# voltageSupplies.net
KiCad netlist of a schematic drawn in Altium Designer
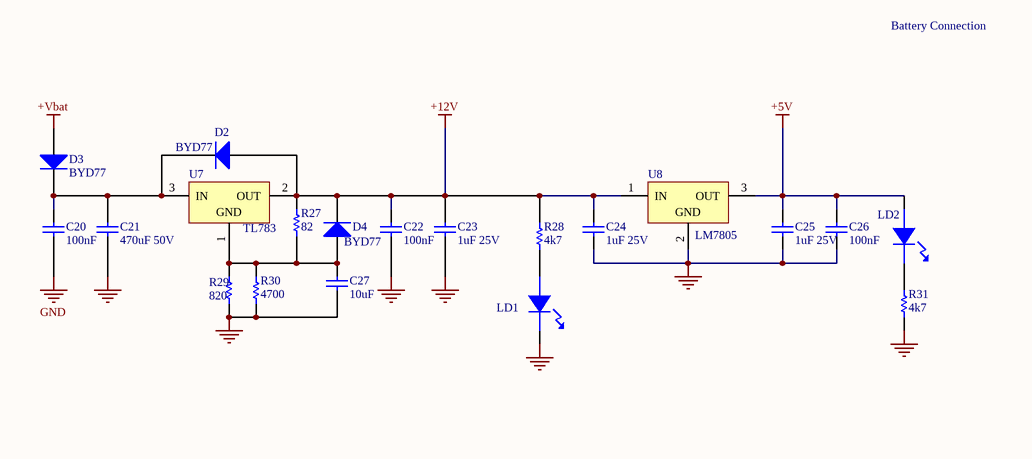
[diagram p0: voltageSupplies.SchDoc]

(export (version "E")
  (design (tool "Eeschema 10.0.6"))
  (components
    (comp (ref "C20")
      (value "100nF")
      (footprint "C1210_M")
      (description "Capacitor")
      (fields (field (name "Comment") "Cap") (field (name "PUBLISHER") "Altium Limited"))
      (libsource (lib "Miscellaneous Devices") (part "Cap"))
    )
    (comp (ref "C21")
      (value "470uF 50V")
      (footprint "CapEltr-Rad4.1-Dpp3.0")
      (description "Capacitor")
      (fields (field (name "Comment") "Cap") (field (name "PUBLISHER") "Altium Limited"))
      (libsource (lib "Miscellaneous Devices") (part "Cap"))
    )
    (comp (ref "C22")
      (value "100nF")
      (footprint "C1210_M")
      (description "Capacitor")
      (fields (field (name "Comment") "Cap") (field (name "PUBLISHER") "Altium Limited"))
      (libsource (lib "Miscellaneous Devices") (part "Cap"))
    )
    (comp (ref "C23")
      (value "1uF 25V")
      (footprint "CapEltr-Rad4.1-Dpp3.0")
      (description "Capacitor")
      (fields (field (name "Comment") "Cap") (field (name "PUBLISHER") "Altium Limited"))
      (libsource (lib "Miscellaneous Devices") (part "Cap"))
    )
    (comp (ref "C24")
      (value "1uF 25V")
      (footprint "CapEltr-Rad4.1-Dpp3.0")
      (description "Capacitor")
      (fields (field (name "Comment") "Cap") (field (name "PUBLISHER") "Altium Limited"))
      (libsource (lib "Miscellaneous Devices") (part "Cap"))
    )
    (comp (ref "C25")
      (value "1uF 25V")
      (footprint "CapEltr-Rad4.1-Dpp3.0")
      (description "Capacitor")
      (fields (field (name "Comment") "Cap") (field (name "PUBLISHER") "Altium Limited"))
      (libsource (lib "Miscellaneous Devices") (part "Cap"))
    )
    (comp (ref "C26")
      (value "100nF")
      (footprint "C1210_M")
      (description "Capacitor")
      (fields (field (name "Comment") "Cap") (field (name "PUBLISHER") "Altium Limited"))
      (libsource (lib "Miscellaneous Devices") (part "Cap"))
    )
    (comp (ref "C27")
      (value "10uF")
      (footprint "C1210_M")
      (description "Capacitor")
      (fields (field (name "Comment") "Cap") (field (name "PUBLISHER") "Altium Limited"))
      (libsource (lib "Miscellaneous Devices") (part "Cap"))
    )
    (comp (ref "D2")
      (value "BYD77")
      (footprint "SOD87")
      (description "1 Amp General Purpose Rectifier")
      (fields (field (name "PUBLISHER") "Altium Limited"))
      (libsource (lib "Miscellaneous Devices") (part "Diode 1N4002"))
    )
    (comp (ref "D3")
      (value "BYD77")
      (footprint "SOD87")
      (description "1 Amp General Purpose Rectifier")
      (fields (field (name "Comment") "Diode 1N4002") (field (name "PUBLISHER") "Altium Limited"))
      (libsource (lib "Miscellaneous Devices") (part "Diode 1N4002"))
    )
    (comp (ref "D4")
      (value "BYD77")
      (footprint "SOD87")
      (description "1 Amp General Purpose Rectifier")
      (fields (field (name "Comment") "1N4002") (field (name "PUBLISHER") "Altium Limited"))
      (libsource (lib "Miscellaneous Devices") (part "Diode 1N4002"))
    )
    (comp (ref "LD1")
      (value "RED")
      (footprint "6-0805_M")
      (description "Diodo Emissor de Luz")
      (libsource (lib "Biblioteca_Guilherme") (part "LED"))
    )
    (comp (ref "LD2")
      (value "RED")
      (footprint "6-0805_M")
      (description "Diodo Emissor de Luz")
      (libsource (lib "Biblioteca_Guilherme") (part "LED"))
    )
    (comp (ref "R27")
      (value "82")
      (footprint "6-0805_M")
      (description "Resistor")
      (fields (field (name "Comment") "Res1") (field (name "PUBLISHER") "Altium Limited"))
      (libsource (lib "Miscellaneous Devices") (part "Res1"))
    )
    (comp (ref "R28")
      (value "4k7")
      (footprint "6-0805_M")
      (description "Resistor")
      (fields (field (name "Comment") "Res1") (field (name "PUBLISHER") "Altium Limited"))
      (libsource (lib "Miscellaneous Devices") (part "Res1"))
    )
    (comp (ref "R29")
      (value "820")
      (footprint "6-0805_M")
      (description "Resistor")
      (fields (field (name "Comment") "Res1") (field (name "PUBLISHER") "Altium Limited"))
      (libsource (lib "Miscellaneous Devices") (part "Res1"))
    )
    (comp (ref "R30")
      (value "4700")
      (footprint "6-0805_M")
      (description "Resistor")
      (fields (field (name "Comment") "Res1") (field (name "PUBLISHER") "Altium Limited"))
      (libsource (lib "Miscellaneous Devices") (part "Res1"))
    )
    (comp (ref "R31")
      (value "4k7")
      (footprint "6-0805_M")
      (description "Resistor")
      (fields (field (name "Comment") "Res1") (field (name "PUBLISHER") "Altium Limited"))
      (libsource (lib "Miscellaneous Devices") (part "Res1"))
    )
    (comp (ref "U7")
      (value "TL783")
      (footprint "TO-220AB")
      (description "Precision 1A Regulator")
      (fields (field (name "PUBLISHER") "Altium Limited"))
      (libsource (lib "ST Power Mgt Voltage Regulator") (part "L7805ACV"))
    )
    (comp (ref "U8")
      (value "LM7805")
      (footprint "TO-220AB")
      (description "Positive-Voltage Regulator")
      (fields (field (name "PUBLISHER") "Altium Limited"))
      (libsource (lib "TI Power Mgt Voltage Regulator") (part "µA7805CKC"))
    )
  )
  (nets
    (net (code "1") (name "+5V") (class "Default")
      (node (ref "C25") (pin "2") (pinfunction "2_2") (pintype "passive"))
      (node (ref "C26") (pin "2") (pinfunction "2_2") (pintype "passive"))
      (node (ref "LD2") (pin "1") (pinfunction "1_1") (pintype "passive"))
      (node (ref "U8") (pin "3") (pinfunction "OUT_3") (pintype "power_in"))
    )
    (net (code "2") (name "+12V") (class "Default")
      (node (ref "C22") (pin "2") (pinfunction "2_2") (pintype "passive"))
      (node (ref "C23") (pin "2") (pinfunction "2_2") (pintype "passive"))
      (node (ref "C24") (pin "2") (pinfunction "2_2") (pintype "passive"))
      (node (ref "D2") (pin "1") (pinfunction "A_1") (pintype "passive"))
      (node (ref "D4") (pin "2") (pinfunction "K_2") (pintype "passive"))
      (node (ref "R27") (pin "1") (pinfunction "1_1") (pintype "passive"))
      (node (ref "R28") (pin "2") (pinfunction "2_2") (pintype "passive"))
      (node (ref "U7") (pin "2") (pinfunction "OUT_2") (pintype "power_in"))
      (node (ref "U8") (pin "1") (pinfunction "IN_1") (pintype "power_in"))
    )
    (net (code "3") (name "+Vbat") (class "Default")
      (node (ref "D3") (pin "1") (pinfunction "A_1") (pintype "passive"))
    )
    (net (code "4") (name "GND") (class "Default")
      (node (ref "C20") (pin "1") (pinfunction "1_1") (pintype "passive"))
      (node (ref "C21") (pin "1") (pinfunction "1_1") (pintype "passive"))
      (node (ref "C22") (pin "1") (pinfunction "1_1") (pintype "passive"))
      (node (ref "C23") (pin "1") (pinfunction "1_1") (pintype "passive"))
      (node (ref "C24") (pin "1") (pinfunction "1_1") (pintype "passive"))
      (node (ref "C25") (pin "1") (pinfunction "1_1") (pintype "passive"))
      (node (ref "C26") (pin "1") (pinfunction "1_1") (pintype "passive"))
      (node (ref "C27") (pin "1") (pinfunction "1_1") (pintype "passive"))
      (node (ref "LD1") (pin "2") (pinfunction "2_2") (pintype "passive"))
      (node (ref "R29") (pin "1") (pinfunction "1_1") (pintype "passive"))
      (node (ref "R30") (pin "1") (pinfunction "1_1") (pintype "passive"))
      (node (ref "R31") (pin "1") (pinfunction "1_1") (pintype "passive"))
      (node (ref "U8") (pin "2") (pinfunction "GND_2") (pintype "power_in"))
    )
    (net (code "5") (name "Net-(D2-K)") (class "Default")
      (node (ref "C20") (pin "2") (pinfunction "2_2") (pintype "passive"))
      (node (ref "C21") (pin "2") (pinfunction "2_2") (pintype "passive"))
      (node (ref "D2") (pin "2") (pinfunction "K_2") (pintype "passive"))
      (node (ref "D3") (pin "2") (pinfunction "K_2") (pintype "passive"))
      (node (ref "U7") (pin "3") (pinfunction "IN_3") (pintype "power_in"))
    )
    (net (code "6") (name "Net-(D4-A)") (class "Default")
      (node (ref "C27") (pin "2") (pinfunction "2_2") (pintype "passive"))
      (node (ref "D4") (pin "1") (pinfunction "A_1") (pintype "passive"))
      (node (ref "R27") (pin "2") (pinfunction "2_2") (pintype "passive"))
      (node (ref "R29") (pin "2") (pinfunction "2_2") (pintype "passive"))
      (node (ref "R30") (pin "2") (pinfunction "2_2") (pintype "passive"))
      (node (ref "U7") (pin "1") (pinfunction "ADJ_1") (pintype "power_in"))
    )
    (net (code "7") (name "Net-(LD1-Pad1)") (class "Default")
      (node (ref "LD1") (pin "1") (pinfunction "1_1") (pintype "passive"))
      (node (ref "R28") (pin "1") (pinfunction "1_1") (pintype "passive"))
    )
    (net (code "8") (name "Net-(LD2-Pad2)") (class "Default")
      (node (ref "LD2") (pin "2") (pinfunction "2_2") (pintype "passive"))
      (node (ref "R31") (pin "2") (pinfunction "2_2") (pintype "passive"))
    )
  )
)
